# commande_neons.net
KiCad netlist of a schematic drawn in EAGLE
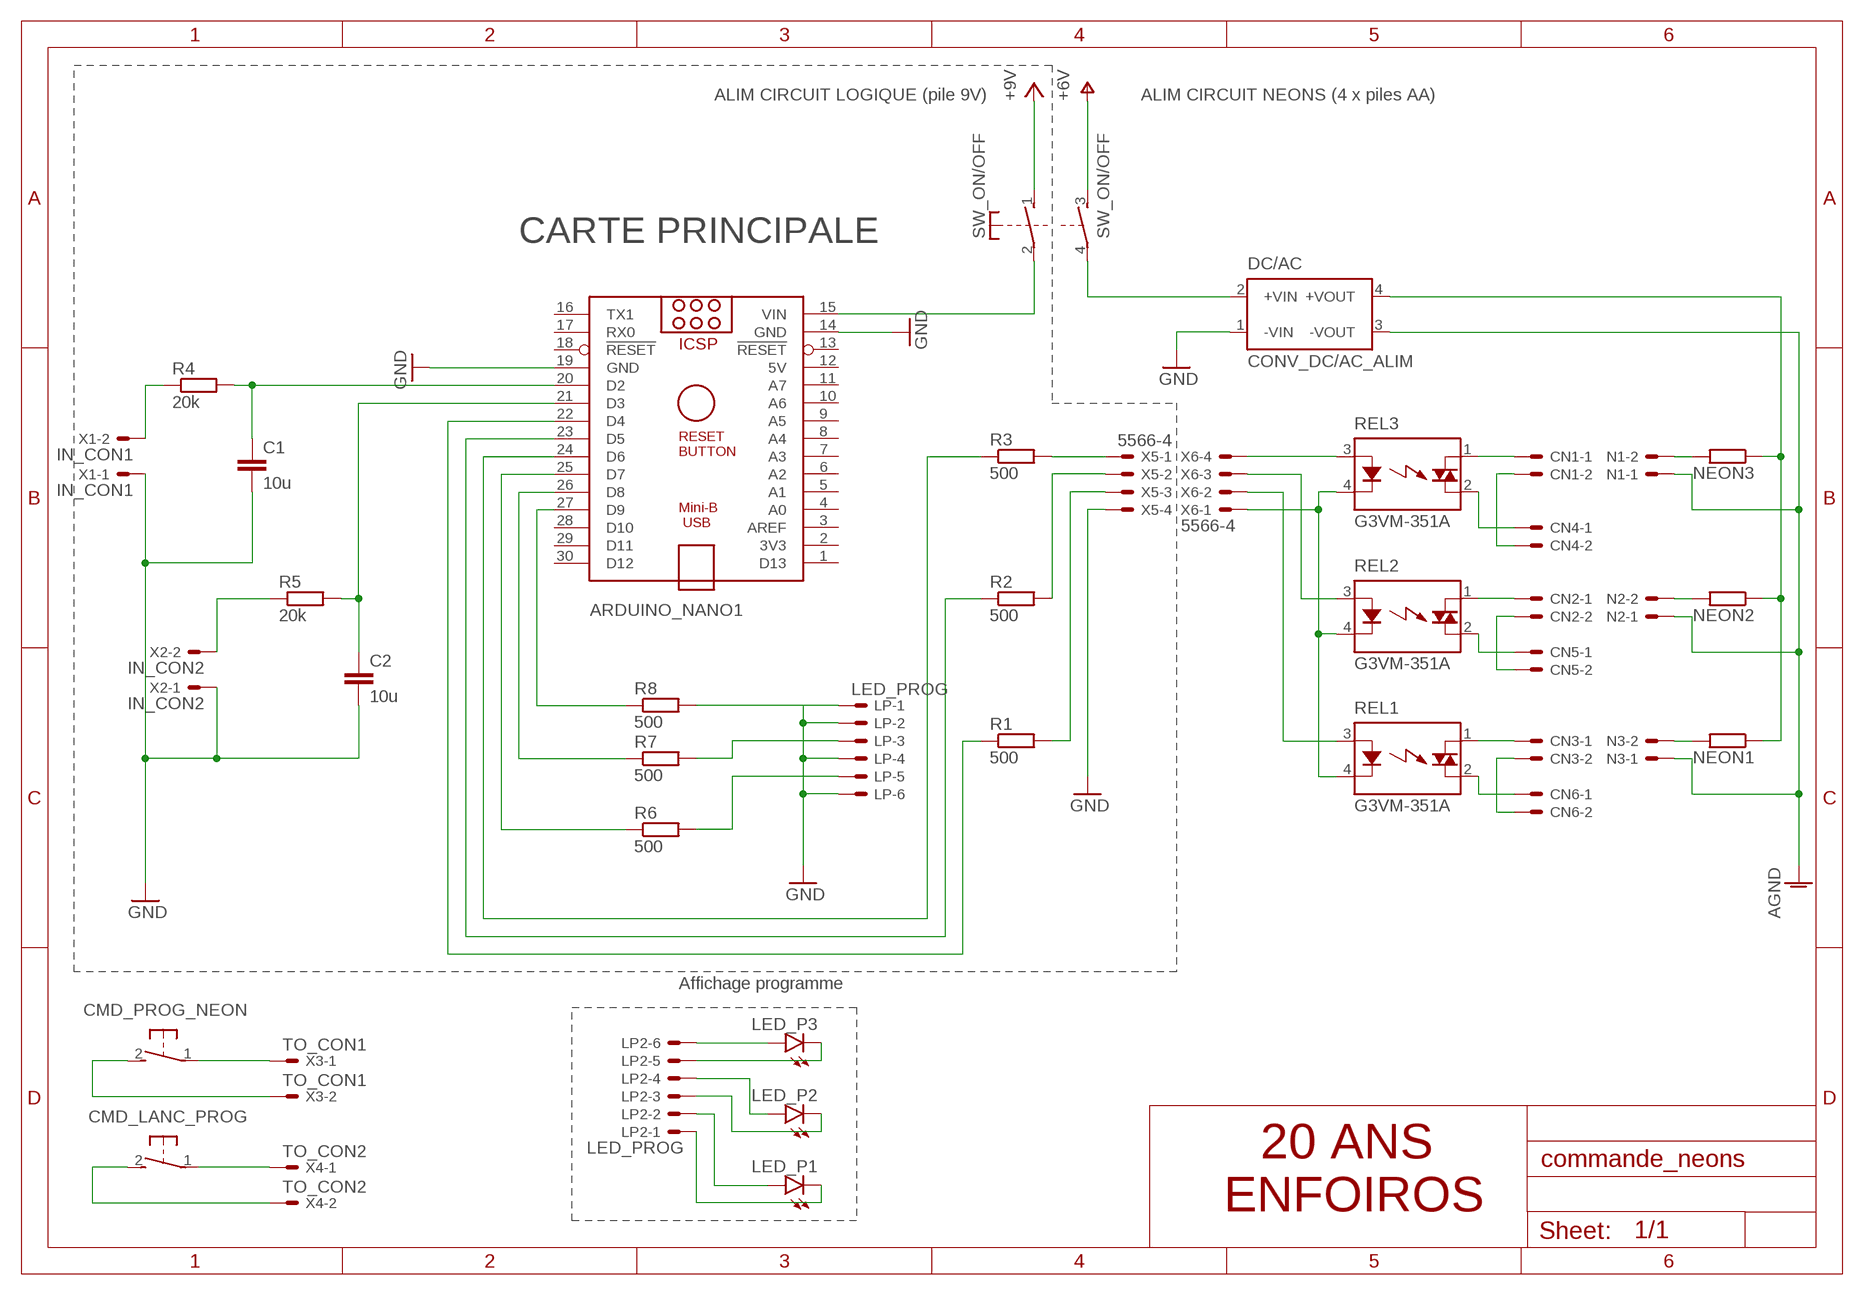
[diagram p0: schematic, sheet 1]

(export (version "E")
  (design (tool "Eeschema 10.0.6"))
  (components
    (comp (ref "ARDUINO_NANO1")
      (value "ARDUINO_NANO")
      (footprint "eagle-import:ARDUINO_NANO")
      (libsource (lib "eagle-import") (part "ARDUINO_NANO"))
    )
    (comp (ref "C1")
      (value "10u")
      (footprint "eagle-import:C025-024X044")
      (libsource (lib "eagle-import") (part "C-EU025-024X044"))
    )
    (comp (ref "C2")
      (value "10u")
      (footprint "eagle-import:C025-024X044")
      (libsource (lib "eagle-import") (part "C-EU025-024X044"))
    )
    (comp (ref "CMD_LANC_PROG")
      (value "31-XX")
      (footprint "eagle-import:B3F-31XX")
      (fields (field (name "MPN") "B3F-3100"))
      (libsource (lib "eagle-import") (part "31-XX"))
    )
    (comp (ref "CMD_PROG_NEON")
      (value "31-XX")
      (footprint "eagle-import:B3F-31XX")
      (fields (field (name "MPN") "B3F-3100"))
      (libsource (lib "eagle-import") (part "31-XX"))
    )
    (comp (ref "CN1")
      (value "22-23-2021")
      (footprint "eagle-import:22-23-2021")
      (fields (field (name "MF") "MOLEX"))
      (libsource (lib "eagle-import") (part "22-23-2021"))
    )
    (comp (ref "CN2")
      (value "22-23-2021")
      (footprint "eagle-import:22-23-2021")
      (fields (field (name "MF") "MOLEX"))
      (libsource (lib "eagle-import") (part "22-23-2021"))
    )
    (comp (ref "CN3")
      (value "22-23-2021")
      (footprint "eagle-import:22-23-2021")
      (fields (field (name "MF") "MOLEX"))
      (libsource (lib "eagle-import") (part "22-23-2021"))
    )
    (comp (ref "CN4")
      (value "22-23-2021")
      (footprint "eagle-import:22-23-2021")
      (fields (field (name "MF") "MOLEX"))
      (libsource (lib "eagle-import") (part "22-23-2021"))
    )
    (comp (ref "CN5")
      (value "22-23-2021")
      (footprint "eagle-import:22-23-2021")
      (fields (field (name "MF") "MOLEX"))
      (libsource (lib "eagle-import") (part "22-23-2021"))
    )
    (comp (ref "CN6")
      (value "22-23-2021")
      (footprint "eagle-import:22-23-2021")
      (fields (field (name "MF") "MOLEX"))
      (libsource (lib "eagle-import") (part "22-23-2021"))
    )
    (comp (ref "DC/AC")
      (value "CONV_DC/AC_ALIM")
      (footprint "eagle-import:TME")
      (fields (field (name "MPN") "TME 0505S"))
      (libsource (lib "eagle-import") (part "TME?0505S"))
    )
    (comp (ref "LED_P1")
      (value "LAP4-BOTTOM")
      (footprint "eagle-import:P47F-BOTTOM")
      (libsource (lib "eagle-import") (part "P4-BOTTOMLA"))
    )
    (comp (ref "LED_P2")
      (value "LAP4-BOTTOM")
      (footprint "eagle-import:P47F-BOTTOM")
      (libsource (lib "eagle-import") (part "P4-BOTTOMLA"))
    )
    (comp (ref "LED_P3")
      (value "LAP4-BOTTOM")
      (footprint "eagle-import:P47F-BOTTOM")
      (libsource (lib "eagle-import") (part "P4-BOTTOMLA"))
    )
    (comp (ref "LP")
      (value "LED_PROG")
      (footprint "eagle-import:5566-6")
      (fields (field (name "MF") "MOLEX") (field (name "MPN") "95566-61002"))
      (libsource (lib "eagle-import") (part "5566-6"))
    )
    (comp (ref "LP2")
      (value "LED_PROG")
      (footprint "eagle-import:5566-6")
      (fields (field (name "MF") "MOLEX") (field (name "MPN") "95566-61002"))
      (libsource (lib "eagle-import") (part "5566-6"))
    )
    (comp (ref "N1")
      (value "22-23-2021")
      (footprint "eagle-import:22-23-2021")
      (fields (field (name "MF") "MOLEX"))
      (libsource (lib "eagle-import") (part "22-23-2021"))
    )
    (comp (ref "N2")
      (value "22-23-2021")
      (footprint "eagle-import:22-23-2021")
      (fields (field (name "MF") "MOLEX"))
      (libsource (lib "eagle-import") (part "22-23-2021"))
    )
    (comp (ref "N3")
      (value "22-23-2021")
      (footprint "eagle-import:22-23-2021")
      (fields (field (name "MF") "MOLEX"))
      (libsource (lib "eagle-import") (part "22-23-2021"))
    )
    (comp (ref "NEON1")
      (value "R-EU_0411/12")
      (footprint "eagle-import:0411_12")
      (libsource (lib "eagle-import") (part "R-EU_0411/12"))
    )
    (comp (ref "NEON2")
      (value "R-EU_0411/12")
      (footprint "eagle-import:0411_12")
      (libsource (lib "eagle-import") (part "R-EU_0411/12"))
    )
    (comp (ref "NEON3")
      (value "R-EU_0411/12")
      (footprint "eagle-import:0411_12")
      (libsource (lib "eagle-import") (part "R-EU_0411/12"))
    )
    (comp (ref "R1")
      (value "500")
      (footprint "eagle-import:0204_7")
      (libsource (lib "eagle-import") (part "R-EU_0204/7"))
    )
    (comp (ref "R2")
      (value "500")
      (footprint "eagle-import:0204_7")
      (libsource (lib "eagle-import") (part "R-EU_0204/7"))
    )
    (comp (ref "R3")
      (value "500")
      (footprint "eagle-import:0204_7")
      (libsource (lib "eagle-import") (part "R-EU_0204/7"))
    )
    (comp (ref "R4")
      (value "20k")
      (footprint "eagle-import:0204_5")
      (libsource (lib "eagle-import") (part "R-EU_0204/5"))
    )
    (comp (ref "R5")
      (value "20k")
      (footprint "eagle-import:0204_5")
      (libsource (lib "eagle-import") (part "R-EU_0204/5"))
    )
    (comp (ref "R6")
      (value "500")
      (footprint "eagle-import:0204_7")
      (libsource (lib "eagle-import") (part "R-EU_0204/7"))
    )
    (comp (ref "R7")
      (value "500")
      (footprint "eagle-import:0204_7")
      (libsource (lib "eagle-import") (part "R-EU_0204/7"))
    )
    (comp (ref "R8")
      (value "500")
      (footprint "eagle-import:0204_7")
      (libsource (lib "eagle-import") (part "R-EU_0204/7"))
    )
    (comp (ref "REL1")
      (value "G3VM-351A")
      (footprint "eagle-import:AQ1-M")
      (fields (field (name "MPN") "AQ5A2-ZP3/28VDC"))
      (libsource (lib "eagle-import") (part "AQ?5A2-ZP3"))
    )
    (comp (ref "REL2")
      (value "G3VM-351A")
      (footprint "eagle-import:AQ1-M")
      (fields (field (name "MPN") "AQ5A2-ZP3/28VDC"))
      (libsource (lib "eagle-import") (part "AQ?5A2-ZP3"))
    )
    (comp (ref "REL3")
      (value "G3VM-351A")
      (footprint "eagle-import:AQ1-M")
      (fields (field (name "MPN") "AQ5A2-ZP3/28VDC"))
      (libsource (lib "eagle-import") (part "AQ?5A2-ZP3"))
    )
    (comp (ref "SW_ON/OFF")
      (value "PVA1")
      (footprint "eagle-import:PVA1F")
      (libsource (lib "eagle-import") (part "PVA1"))
    )
    (comp (ref "X1")
      (value "IN_CON1")
      (footprint "eagle-import:332-02")
      (libsource (lib "eagle-import") (part "332-02"))
    )
    (comp (ref "X2")
      (value "IN_CON2")
      (footprint "eagle-import:332-02")
      (libsource (lib "eagle-import") (part "332-02"))
    )
    (comp (ref "X3")
      (value "TO_CON1")
      (footprint "eagle-import:332-02")
      (libsource (lib "eagle-import") (part "332-02"))
    )
    (comp (ref "X4")
      (value "TO_CON2")
      (footprint "eagle-import:332-02")
      (libsource (lib "eagle-import") (part "332-02"))
    )
    (comp (ref "X5")
      (value "5566-4")
      (footprint "eagle-import:5566-4")
      (fields (field (name "MF") "MOLEX"))
      (libsource (lib "eagle-import") (part "5566-4"))
    )
    (comp (ref "X6")
      (value "5566-4")
      (footprint "eagle-import:5566-4")
      (fields (field (name "MF") "MOLEX"))
      (libsource (lib "eagle-import") (part "5566-4"))
    )
  )
  (nets
    (net (code "1") (name "+6V") (class "Default")
      (node (ref "SW_ON/OFF") (pin "3") (pinfunction "S_3") (pintype "passive"))
    )
    (net (code "2") (name "+9V") (class "Default")
      (node (ref "SW_ON/OFF") (pin "1") (pinfunction "S_1") (pintype "passive"))
    )
    (net (code "3") (name "/5V") (class "Default")
      (node (ref "ARDUINO_NANO1") (pin "12") (pinfunction "5V_12") (pintype "power_in"))
    )
    (net (code "4") (name "AGND") (class "Default")
      (node (ref "DC/AC") (pin "3") (pinfunction "-VOUT_3") (pintype "passive"))
      (node (ref "N1") (pin "1") (pinfunction "S_1") (pintype "passive"))
      (node (ref "N2") (pin "1") (pinfunction "S_1") (pintype "passive"))
      (node (ref "N3") (pin "1") (pinfunction "S_1") (pintype "passive"))
    )
    (net (code "5") (name "GND") (class "Default")
      (node (ref "ARDUINO_NANO1") (pin "14") (pinfunction "GND_14") (pintype "power_in"))
      (node (ref "ARDUINO_NANO1") (pin "19") (pinfunction "GND_19") (pintype "power_in"))
      (node (ref "C1") (pin "2") (pinfunction "2_2") (pintype "passive"))
      (node (ref "C2") (pin "2") (pinfunction "2_2") (pintype "passive"))
      (node (ref "DC/AC") (pin "1") (pinfunction "-VIN_1") (pintype "passive"))
      (node (ref "LP") (pin "2") (pinfunction "S_2") (pintype "passive"))
      (node (ref "LP") (pin "4") (pinfunction "S_4") (pintype "passive"))
      (node (ref "LP") (pin "6") (pinfunction "S_6") (pintype "passive"))
      (node (ref "X1") (pin "1") (pinfunction "S_1") (pintype "passive"))
      (node (ref "X2") (pin "1") (pinfunction "S_1") (pintype "passive"))
      (node (ref "X5") (pin "4") (pinfunction "S_4") (pintype "passive"))
    )
    (net (code "6") (name "Net-(ARDUINO_NANO1-D2)") (class "Default")
      (node (ref "ARDUINO_NANO1") (pin "20") (pinfunction "D2_20") (pintype "bidirectional"))
      (node (ref "C1") (pin "1") (pinfunction "1_1") (pintype "passive"))
      (node (ref "R4") (pin "2") (pinfunction "2_2") (pintype "passive"))
    )
    (net (code "7") (name "Net-(ARDUINO_NANO1-D3)") (class "Default")
      (node (ref "ARDUINO_NANO1") (pin "21") (pinfunction "D3_21") (pintype "bidirectional"))
      (node (ref "C2") (pin "1") (pinfunction "1_1") (pintype "passive"))
      (node (ref "R5") (pin "2") (pinfunction "2_2") (pintype "passive"))
    )
    (net (code "8") (name "Net-(ARDUINO_NANO1-D4)") (class "Default")
      (node (ref "ARDUINO_NANO1") (pin "22") (pinfunction "D4_22") (pintype "bidirectional"))
      (node (ref "R1") (pin "1") (pinfunction "1_1") (pintype "passive"))
    )
    (net (code "9") (name "Net-(ARDUINO_NANO1-D5)") (class "Default")
      (node (ref "ARDUINO_NANO1") (pin "23") (pinfunction "D5_23") (pintype "bidirectional"))
      (node (ref "R2") (pin "1") (pinfunction "1_1") (pintype "passive"))
    )
    (net (code "10") (name "Net-(ARDUINO_NANO1-D6)") (class "Default")
      (node (ref "ARDUINO_NANO1") (pin "24") (pinfunction "D6_24") (pintype "bidirectional"))
      (node (ref "R3") (pin "1") (pinfunction "1_1") (pintype "passive"))
    )
    (net (code "11") (name "Net-(ARDUINO_NANO1-D7)") (class "Default")
      (node (ref "ARDUINO_NANO1") (pin "25") (pinfunction "D7_25") (pintype "bidirectional"))
      (node (ref "R6") (pin "1") (pinfunction "1_1") (pintype "passive"))
    )
    (net (code "12") (name "Net-(ARDUINO_NANO1-D8)") (class "Default")
      (node (ref "ARDUINO_NANO1") (pin "26") (pinfunction "D8_26") (pintype "bidirectional"))
      (node (ref "R7") (pin "1") (pinfunction "1_1") (pintype "passive"))
    )
    (net (code "13") (name "Net-(ARDUINO_NANO1-D9)") (class "Default")
      (node (ref "ARDUINO_NANO1") (pin "27") (pinfunction "D9_27") (pintype "bidirectional"))
      (node (ref "R8") (pin "1") (pinfunction "1_1") (pintype "passive"))
    )
    (net (code "14") (name "Net-(ARDUINO_NANO1-VIN)") (class "Default")
      (node (ref "ARDUINO_NANO1") (pin "15") (pinfunction "VIN_15") (pintype "power_in"))
      (node (ref "SW_ON/OFF") (pin "2") (pinfunction "P_2") (pintype "passive"))
    )
    (net (code "15") (name "Net-(CMD_LANC_PROG-P)") (class "Default")
      (node (ref "CMD_LANC_PROG") (pin "1") (pinfunction "P_1") (pintype "passive"))
      (node (ref "X4") (pin "1") (pinfunction "S_1") (pintype "passive"))
    )
    (net (code "16") (name "Net-(CMD_LANC_PROG-S)") (class "Default")
      (node (ref "CMD_LANC_PROG") (pin "2") (pinfunction "S_2") (pintype "passive"))
      (node (ref "X4") (pin "2") (pinfunction "S_2") (pintype "passive"))
    )
    (net (code "17") (name "Net-(CMD_PROG_NEON-P)") (class "Default")
      (node (ref "CMD_PROG_NEON") (pin "1") (pinfunction "P_1") (pintype "passive"))
      (node (ref "X3") (pin "1") (pinfunction "S_1") (pintype "passive"))
    )
    (net (code "18") (name "Net-(CMD_PROG_NEON-S)") (class "Default")
      (node (ref "CMD_PROG_NEON") (pin "2") (pinfunction "S_2") (pintype "passive"))
      (node (ref "X3") (pin "2") (pinfunction "S_2") (pintype "passive"))
    )
    (net (code "19") (name "Net-(CN1A-S)") (class "Default")
      (node (ref "CN1") (pin "1") (pinfunction "S_1") (pintype "passive"))
      (node (ref "REL3") (pin "1") (pinfunction "DS1_1") (pintype "passive"))
    )
    (net (code "20") (name "Net-(CN1B-S)") (class "Default")
      (node (ref "CN1") (pin "2") (pinfunction "S_2") (pintype "passive"))
      (node (ref "CN4") (pin "2") (pinfunction "S_2") (pintype "passive"))
    )
    (net (code "21") (name "Net-(CN2A-S)") (class "Default")
      (node (ref "CN2") (pin "1") (pinfunction "S_1") (pintype "passive"))
      (node (ref "REL2") (pin "1") (pinfunction "DS1_1") (pintype "passive"))
    )
    (net (code "22") (name "Net-(CN2B-S)") (class "Default")
      (node (ref "CN2") (pin "2") (pinfunction "S_2") (pintype "passive"))
      (node (ref "CN5") (pin "2") (pinfunction "S_2") (pintype "passive"))
    )
    (net (code "23") (name "Net-(CN3A-S)") (class "Default")
      (node (ref "CN3") (pin "1") (pinfunction "S_1") (pintype "passive"))
      (node (ref "REL1") (pin "1") (pinfunction "DS1_1") (pintype "passive"))
    )
    (net (code "24") (name "Net-(CN3B-S)") (class "Default")
      (node (ref "CN3") (pin "2") (pinfunction "S_2") (pintype "passive"))
      (node (ref "CN6") (pin "2") (pinfunction "S_2") (pintype "passive"))
    )
    (net (code "25") (name "Net-(CN4A-S)") (class "Default")
      (node (ref "CN4") (pin "1") (pinfunction "S_1") (pintype "passive"))
      (node (ref "REL3") (pin "2") (pinfunction "DS2_2") (pintype "passive"))
    )
    (net (code "26") (name "Net-(CN5A-S)") (class "Default")
      (node (ref "CN5") (pin "1") (pinfunction "S_1") (pintype "passive"))
      (node (ref "REL2") (pin "2") (pinfunction "DS2_2") (pintype "passive"))
    )
    (net (code "27") (name "Net-(CN6A-S)") (class "Default")
      (node (ref "CN6") (pin "1") (pinfunction "S_1") (pintype "passive"))
      (node (ref "REL1") (pin "2") (pinfunction "DS2_2") (pintype "passive"))
    )
    (net (code "28") (name "Net-(DC/AC-+VIN)") (class "Default")
      (node (ref "DC/AC") (pin "2") (pinfunction "+VIN_2") (pintype "passive"))
      (node (ref "SW_ON/OFF") (pin "4") (pinfunction "P_4") (pintype "passive"))
    )
    (net (code "29") (name "Net-(DC/AC-+VOUT)") (class "Default")
      (node (ref "DC/AC") (pin "4") (pinfunction "+VOUT_4") (pintype "passive"))
      (node (ref "NEON1") (pin "1") (pinfunction "1_1") (pintype "passive"))
      (node (ref "NEON2") (pin "1") (pinfunction "1_1") (pintype "passive"))
      (node (ref "NEON3") (pin "1") (pinfunction "1_1") (pintype "passive"))
    )
    (net (code "30") (name "Net-(LP2A-S)") (class "Default")
      (node (ref "LED_P1") (pin "C") (pinfunction "C_C") (pintype "passive"))
      (node (ref "LP2") (pin "1") (pinfunction "S_1") (pintype "passive"))
    )
    (net (code "31") (name "Net-(LP2B-S)") (class "Default")
      (node (ref "LED_P1") (pin "A") (pinfunction "A_A") (pintype "passive"))
      (node (ref "LP2") (pin "2") (pinfunction "S_2") (pintype "passive"))
    )
    (net (code "32") (name "Net-(LP2C-S)") (class "Default")
      (node (ref "LED_P2") (pin "C") (pinfunction "C_C") (pintype "passive"))
      (node (ref "LP2") (pin "3") (pinfunction "S_3") (pintype "passive"))
    )
    (net (code "33") (name "Net-(LP2D-S)") (class "Default")
      (node (ref "LED_P2") (pin "A") (pinfunction "A_A") (pintype "passive"))
      (node (ref "LP2") (pin "4") (pinfunction "S_4") (pintype "passive"))
    )
    (net (code "34") (name "Net-(LP2E-S)") (class "Default")
      (node (ref "LED_P3") (pin "C") (pinfunction "C_C") (pintype "passive"))
      (node (ref "LP2") (pin "5") (pinfunction "S_5") (pintype "passive"))
    )
    (net (code "35") (name "Net-(LP2F-S)") (class "Default")
      (node (ref "LED_P3") (pin "A") (pinfunction "A_A") (pintype "passive"))
      (node (ref "LP2") (pin "6") (pinfunction "S_6") (pintype "passive"))
    )
    (net (code "36") (name "Net-(LPA-S)") (class "Default")
      (node (ref "LP") (pin "1") (pinfunction "S_1") (pintype "passive"))
      (node (ref "R8") (pin "2") (pinfunction "2_2") (pintype "passive"))
    )
    (net (code "37") (name "Net-(LPC-S)") (class "Default")
      (node (ref "LP") (pin "3") (pinfunction "S_3") (pintype "passive"))
      (node (ref "R7") (pin "2") (pinfunction "2_2") (pintype "passive"))
    )
    (net (code "38") (name "Net-(LPE-S)") (class "Default")
      (node (ref "LP") (pin "5") (pinfunction "S_5") (pintype "passive"))
      (node (ref "R6") (pin "2") (pinfunction "2_2") (pintype "passive"))
    )
    (net (code "39") (name "Net-(N1B-S)") (class "Default")
      (node (ref "N1") (pin "2") (pinfunction "S_2") (pintype "passive"))
      (node (ref "NEON3") (pin "2") (pinfunction "2_2") (pintype "passive"))
    )
    (net (code "40") (name "Net-(N2B-S)") (class "Default")
      (node (ref "N2") (pin "2") (pinfunction "S_2") (pintype "passive"))
      (node (ref "NEON2") (pin "2") (pinfunction "2_2") (pintype "passive"))
    )
    (net (code "41") (name "Net-(N3B-S)") (class "Default")
      (node (ref "N3") (pin "2") (pinfunction "S_2") (pintype "passive"))
      (node (ref "NEON1") (pin "2") (pinfunction "2_2") (pintype "passive"))
    )
    (net (code "42") (name "Net-(REL1-A)") (class "Default")
      (node (ref "REL1") (pin "3") (pinfunction "A_3") (pintype "passive"))
      (node (ref "X6") (pin "2") (pinfunction "S_2") (pintype "passive"))
    )
    (net (code "43") (name "Net-(REL1-K)") (class "Default")
      (node (ref "REL1") (pin "4") (pinfunction "K_4") (pintype "passive"))
      (node (ref "REL2") (pin "4") (pinfunction "K_4") (pintype "passive"))
      (node (ref "REL3") (pin "4") (pinfunction "K_4") (pintype "passive"))
      (node (ref "X6") (pin "1") (pinfunction "S_1") (pintype "passive"))
    )
    (net (code "44") (name "Net-(REL2-A)") (class "Default")
      (node (ref "REL2") (pin "3") (pinfunction "A_3") (pintype "passive"))
      (node (ref "X6") (pin "3") (pinfunction "S_3") (pintype "passive"))
    )
    (net (code "45") (name "Net-(REL3-A)") (class "Default")
      (node (ref "REL3") (pin "3") (pinfunction "A_3") (pintype "passive"))
      (node (ref "X6") (pin "4") (pinfunction "S_4") (pintype "passive"))
    )
    (net (code "46") (name "Net-(X1B-S)") (class "Default")
      (node (ref "R4") (pin "1") (pinfunction "1_1") (pintype "passive"))
      (node (ref "X1") (pin "2") (pinfunction "S_2") (pintype "passive"))
    )
    (net (code "47") (name "Net-(X2B-S)") (class "Default")
      (node (ref "R5") (pin "1") (pinfunction "1_1") (pintype "passive"))
      (node (ref "X2") (pin "2") (pinfunction "S_2") (pintype "passive"))
    )
    (net (code "48") (name "Net-(X5A-S)") (class "Default")
      (node (ref "R3") (pin "2") (pinfunction "2_2") (pintype "passive"))
      (node (ref "X5") (pin "1") (pinfunction "S_1") (pintype "passive"))
    )
    (net (code "49") (name "Net-(X5B-S)") (class "Default")
      (node (ref "R2") (pin "2") (pinfunction "2_2") (pintype "passive"))
      (node (ref "X5") (pin "2") (pinfunction "S_2") (pintype "passive"))
    )
    (net (code "50") (name "Net-(X5C-S)") (class "Default")
      (node (ref "R1") (pin "2") (pinfunction "2_2") (pintype "passive"))
      (node (ref "X5") (pin "3") (pinfunction "S_3") (pintype "passive"))
    )
    (net (code "51") (name "unconnected-(ARDUINO_NANO1-3V3-Pad2)") (class "Default")
      (node (ref "ARDUINO_NANO1") (pin "2") (pinfunction "3V3_2") (pintype "output"))
    )
    (net (code "52") (name "unconnected-(ARDUINO_NANO1-A0-Pad4)") (class "Default")
      (node (ref "ARDUINO_NANO1") (pin "4") (pinfunction "A0_4") (pintype "bidirectional"))
    )
    (net (code "53") (name "unconnected-(ARDUINO_NANO1-A1-Pad5)") (class "Default")
      (node (ref "ARDUINO_NANO1") (pin "5") (pinfunction "A1_5") (pintype "bidirectional"))
    )
    (net (code "54") (name "unconnected-(ARDUINO_NANO1-A2-Pad6)") (class "Default")
      (node (ref "ARDUINO_NANO1") (pin "6") (pinfunction "A2_6") (pintype "bidirectional"))
    )
    (net (code "55") (name "unconnected-(ARDUINO_NANO1-A3-Pad7)") (class "Default")
      (node (ref "ARDUINO_NANO1") (pin "7") (pinfunction "A3_7") (pintype "bidirectional"))
    )
    (net (code "56") (name "unconnected-(ARDUINO_NANO1-A4-Pad8)") (class "Default")
      (node (ref "ARDUINO_NANO1") (pin "8") (pinfunction "A4_8") (pintype "bidirectional"))
    )
    (net (code "57") (name "unconnected-(ARDUINO_NANO1-A5-Pad9)") (class "Default")
      (node (ref "ARDUINO_NANO1") (pin "9") (pinfunction "A5_9") (pintype "bidirectional"))
    )
    (net (code "58") (name "unconnected-(ARDUINO_NANO1-A6-Pad10)") (class "Default")
      (node (ref "ARDUINO_NANO1") (pin "10") (pinfunction "A6_10") (pintype "bidirectional"))
    )
    (net (code "59") (name "unconnected-(ARDUINO_NANO1-A7-Pad11)") (class "Default")
      (node (ref "ARDUINO_NANO1") (pin "11") (pinfunction "A7_11") (pintype "bidirectional"))
    )
    (net (code "60") (name "unconnected-(ARDUINO_NANO1-AREF-Pad3)") (class "Default")
      (node (ref "ARDUINO_NANO1") (pin "3") (pinfunction "AREF_3") (pintype "input"))
    )
    (net (code "61") (name "unconnected-(ARDUINO_NANO1-D10-Pad28)") (class "Default")
      (node (ref "ARDUINO_NANO1") (pin "28") (pinfunction "D10_28") (pintype "bidirectional"))
    )
    (net (code "62") (name "unconnected-(ARDUINO_NANO1-D11-Pad29)") (class "Default")
      (node (ref "ARDUINO_NANO1") (pin "29") (pinfunction "D11_29") (pintype "bidirectional"))
    )
    (net (code "63") (name "unconnected-(ARDUINO_NANO1-D12-Pad30)") (class "Default")
      (node (ref "ARDUINO_NANO1") (pin "30") (pinfunction "D12_30") (pintype "bidirectional"))
    )
    (net (code "64") (name "unconnected-(ARDUINO_NANO1-D13-Pad1)") (class "Default")
      (node (ref "ARDUINO_NANO1") (pin "1") (pinfunction "D13_1") (pintype "bidirectional"))
    )
    (net (code "65") (name "unconnected-(ARDUINO_NANO1-RX0-Pad17)") (class "Default")
      (node (ref "ARDUINO_NANO1") (pin "17") (pinfunction "RX0_17") (pintype "bidirectional"))
    )
    (net (code "66") (name "unconnected-(ARDUINO_NANO1-TX1-Pad16)") (class "Default")
      (node (ref "ARDUINO_NANO1") (pin "16") (pinfunction "TX1_16") (pintype "bidirectional"))
    )
    (net (code "67") (name "unconnected-(ARDUINO_NANO1-~{RESET}-Pad13)") (class "Default")
      (node (ref "ARDUINO_NANO1") (pin "13") (pinfunction "~{RESET}_13") (pintype "input"))
    )
    (net (code "68") (name "unconnected-(ARDUINO_NANO1-~{RESET}-Pad18)") (class "Default")
      (node (ref "ARDUINO_NANO1") (pin "18") (pinfunction "~{RESET}_18") (pintype "input"))
    )
  )
)
